# Base.net
KiCad netlist of a schematic drawn in Altium Designer
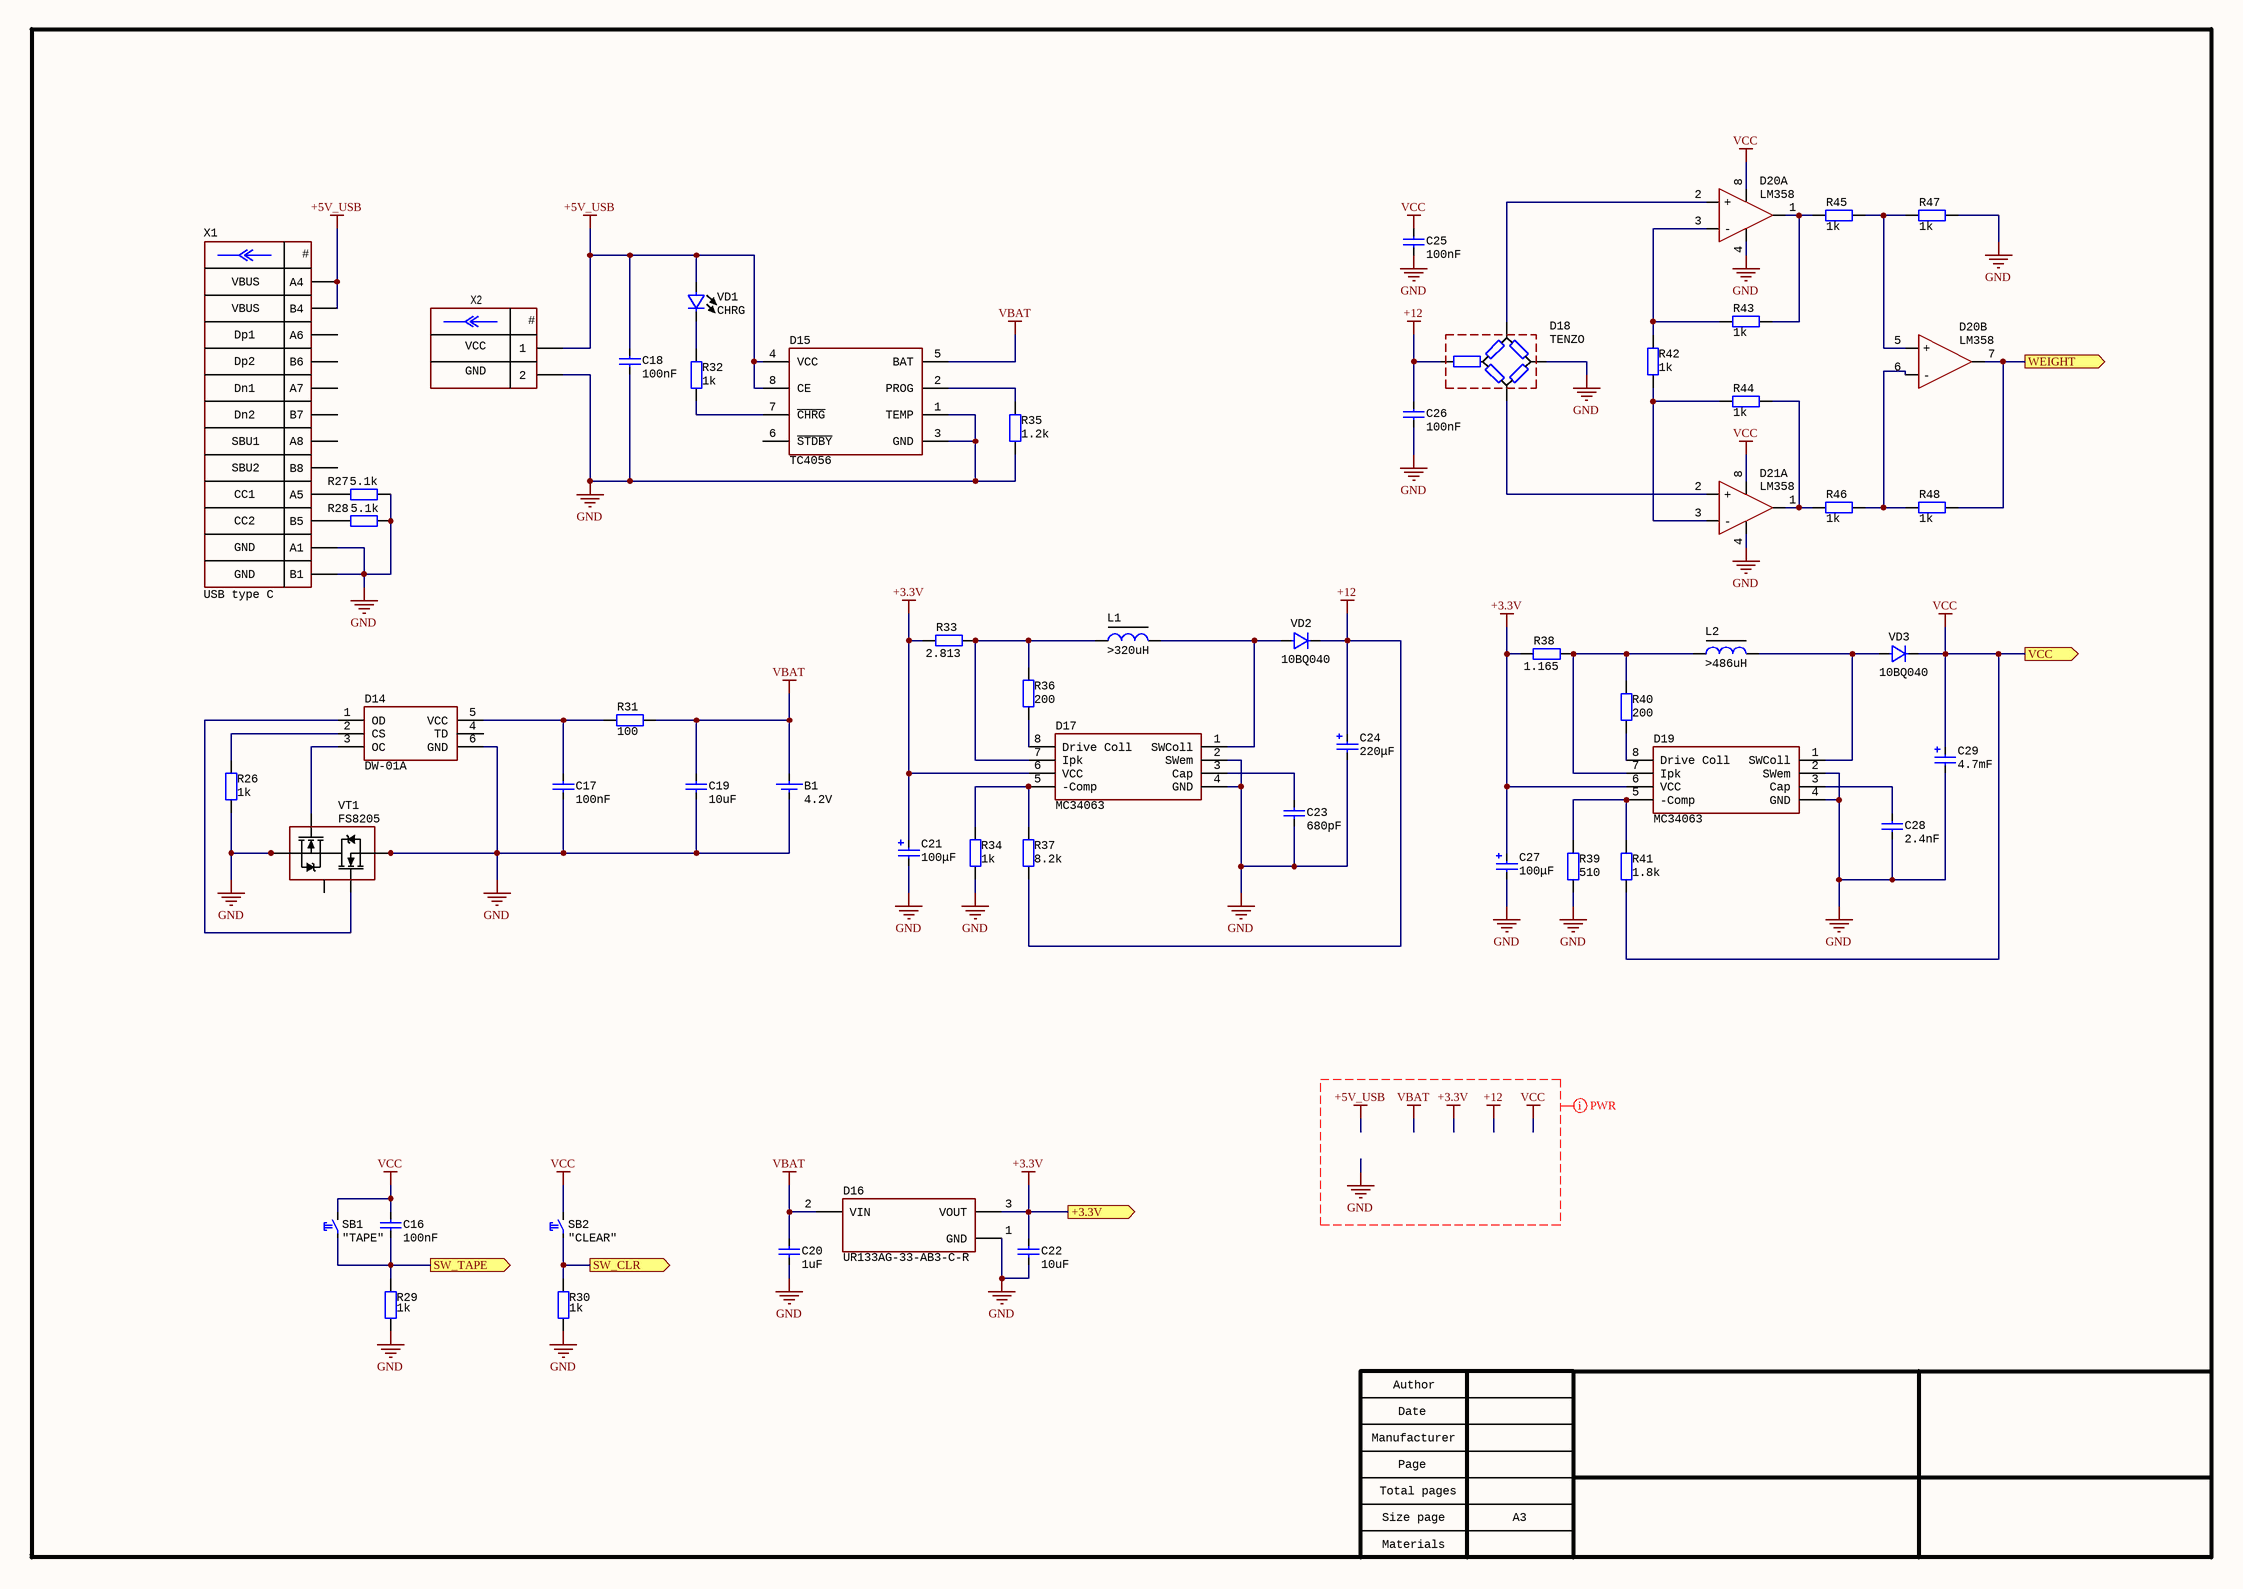
[diagram p0: Base.SchDoc]

(export (version "E")
  (design (tool "Eeschema 10.0.6"))
  (components
    (comp (ref "B1")
      (value "~")
      (footprint "CON: PLS-2")
      (fields
        (field (name "MANUFACTURER") "ALLOYSEED")
        (field (name "VALUEMANUFACTURERPARTNUMBER") "Single holder 18650, 4.2V")
        (field (name "PARTNUMBER") "Holder 18650")
        (field (name "VOLTAGEMAX") "4.2V")
      )
      (libsource (lib "connector") (part "Battery PLS-2"))
    )
    (comp (ref "C16")
      (value "100nF")
      (footprint "CAP: ECHU(X) K (0603)")
      (fields
        (field (name "MANUFACTURER") "Epcos")
        (field (name "PARTNUMBER") "B32774D4106K000")
        (field (name "VALUEMANUFACTURERPARTNUMBER") "Film capacitor, 100nF, 15VDC, ±10%, 10.9mOhm, 31.5x15 mm, -40...+105°C")
      )
      (libsource (lib "capacitor") (part "Film"))
    )
    (comp (ref "C17")
      (value "100nF")
      (footprint "CAP: ECHU(X) K (0603)")
      (fields
        (field (name "MANUFACTURER") "Epcos")
        (field (name "PARTNUMBER") "B32774D4106K000")
        (field (name "VALUEMANUFACTURERPARTNUMBER") "Film capacitor, 100nF, 15VDC, ±10%, 10.9mOhm, 31.5x15 mm, -40...+105°C")
      )
      (libsource (lib "capacitor") (part "Film"))
    )
    (comp (ref "C18")
      (value "100nF")
      (footprint "CAP: ECHU(X) K (0603)")
      (fields
        (field (name "MANUFACTURER") "Epcos")
        (field (name "PARTNUMBER") "B32774D4106K000")
        (field (name "VALUEMANUFACTURERPARTNUMBER") "Film capacitor, 100nF, 15VDC, ±10%, 10.9mOhm, 31.5x15 mm, -40...+105°C")
      )
      (libsource (lib "capacitor") (part "Film"))
    )
    (comp (ref "C19")
      (value "10uF")
      (footprint "CAP: ECHU(X) K (0603)")
      (fields
        (field (name "MANUFACTURER") "Epcos")
        (field (name "PARTNUMBER") "B32774D4106K000")
        (field (name "VALUEMANUFACTURERPARTNUMBER") "Film capacitor, 10uF, 15VDC, ±10%, 10.9mOhm, 31.5x15 mm, -40...+105°C")
      )
      (libsource (lib "capacitor") (part "Film"))
    )
    (comp (ref "C20")
      (value "1uF")
      (footprint "CAP: ECHU(X) K (0603)")
      (fields
        (field (name "MANUFACTURER") "Epcos")
        (field (name "PARTNUMBER") "B32774D4106K000")
        (field (name "VALUEMANUFACTURERPARTNUMBER") "Film capacitor, 1uF, 15VDC, ±10%, 10.9mOhm, 31.5x15 mm, -40...+105°C")
      )
      (libsource (lib "capacitor") (part "Film"))
    )
    (comp (ref "C21")
      (value "100μF")
      (footprint "CAP: TANTAL-E")
      (fields
        (field (name "MANUFACTURER") "AVX")
        (field (name "PARTNUMBER") "F930J107KAAAJ6")
        (field (name "VALUEMANUFACTURERPARTNUMBER") "Tantalum capacitor, 100μF, 6.3V, ±10%, 2Ohm, case A (3216), -55...+125°C")
      )
      (libsource (lib "capacitor") (part "Tantal"))
    )
    (comp (ref "C22")
      (value "10uF")
      (footprint "CAP: ECHU(X) K (0603)")
      (fields
        (field (name "MANUFACTURER") "Epcos")
        (field (name "PARTNUMBER") "B32774D4106K000")
        (field (name "VALUEMANUFACTURERPARTNUMBER") "Film capacitor, 10uF, 15VDC, ±10%, 10.9mOhm, 31.5x15 mm, -40...+105°C")
      )
      (libsource (lib "capacitor") (part "Film"))
    )
    (comp (ref "C23")
      (value "680pF")
      (footprint "CAP: ECHU(X) J (0805)")
      (fields
        (field (name "MANUFACTURER") "Epcos")
        (field (name "PARTNUMBER") "B32774D4106K000")
        (field (name "VALUEMANUFACTURERPARTNUMBER") "Film capacitor, 680pF, 15VDC, ±10%, 10.9mOhm, 31.5x15 mm, -40...+105°C")
      )
      (libsource (lib "capacitor") (part "Film"))
    )
    (comp (ref "C24")
      (value "220μF")
      (footprint "CAP: TANTAL-E")
      (fields
        (field (name "MANUFACTURER") "AVX")
        (field (name "PARTNUMBER") "F930J107KAAAJ6")
        (field (name "VALUEMANUFACTURERPARTNUMBER") "Tantalum capacitor, 220μF, 6.3V, ±10%, 2Ohm, case A (3216), -55...+125°C")
      )
      (libsource (lib "capacitor") (part "Tantal"))
    )
    (comp (ref "C25")
      (value "100nF")
      (footprint "CAP: ECHU(X) K (0603)")
      (fields
        (field (name "MANUFACTURER") "Epcos")
        (field (name "PARTNUMBER") "B32774D4106K000")
        (field (name "VALUEMANUFACTURERPARTNUMBER") "Film capacitor, 100nF, 15VDC, ±10%, 10.9mOhm, 31.5x15 mm, -40...+105°C")
      )
      (libsource (lib "capacitor") (part "Film"))
    )
    (comp (ref "C26")
      (value "100nF")
      (footprint "CAP: ECHU(X) K (0603)")
      (fields
        (field (name "MANUFACTURER") "Epcos")
        (field (name "PARTNUMBER") "B32774D4106K000")
        (field (name "VALUEMANUFACTURERPARTNUMBER") "Film capacitor, 100nF, 15VDC, ±10%, 10.9mOhm, 31.5x15 mm, -40...+105°C")
      )
      (libsource (lib "capacitor") (part "Film"))
    )
    (comp (ref "C27")
      (value "100μF")
      (footprint "CAP: TANTAL-E")
      (fields
        (field (name "MANUFACTURER") "AVX")
        (field (name "PARTNUMBER") "F930J107KAAAJ6")
        (field (name "VALUEMANUFACTURERPARTNUMBER") "Tantalum capacitor, 100μF, 6.3V, ±10%, 2Ohm, case A (3216), -55...+125°C")
      )
      (libsource (lib "capacitor") (part "Tantal"))
    )
    (comp (ref "C28")
      (value "2.4nF")
      (footprint "CAP: ECHU(X) J (0805)")
      (fields
        (field (name "MANUFACTURER") "Epcos")
        (field (name "PARTNUMBER") "B32774D4106K000")
        (field (name "VALUEMANUFACTURERPARTNUMBER") "Film capacitor, 2.4nF, 15VDC, ±10%, 10.9mOhm, 31.5x15 mm, -40...+105°C")
      )
      (libsource (lib "capacitor") (part "Film"))
    )
    (comp (ref "C29")
      (value "4.7mF")
      (footprint "CAP: TANTAL-E")
      (fields
        (field (name "MANUFACTURER") "AVX")
        (field (name "PARTNUMBER") "F930J107KAAAJ6")
        (field (name "VALUEMANUFACTURERPARTNUMBER") "Tantalum capacitor, 4.7mF, 6.3V, ±10%, 2Ohm, case A (3216), -55...+125°C")
      )
      (libsource (lib "capacitor") (part "Tantal"))
    )
    (comp (ref "D14")
      (value "DW-01A")
      (footprint "SOT23-6")
      (fields
        (field (name "PARTNUMBER") "LTC4056ETS8-4.2#TRMPBF")
        (field (name "MANUFACTURER") "Linear Technology")
      )
      (libsource (lib "ic-power-supply") (part "DW-01A"))
    )
    (comp (ref "D15")
      (value "TC4056")
      (footprint "8-SOIC")
      (fields
        (field (name "PARTNUMBER") "LTC4056ETS8-4.2#TRMPBF")
        (field (name "MANUFACTURER") "Linear Technology")
      )
      (libsource (lib "ic-power-supply") (part "TC4056"))
    )
    (comp (ref "D16")
      (value "~")
      (footprint "SOT-89")
      (description "Linear voltage regulator")
      (fields
        (field (name "MANUFACTURER") "Diodes Incorporated")
        (field (name "VALUEMANUFACTURERPARTNUMBER") "Linear voltage regulator, input 2.5...6V, 0.7V, output 1.8V, 0.3A, -40...+85°C, SOT23-5")
        (field (name "PARTNUMBER") "UR133AG-33-AB3-C-R")
      )
      (libsource (lib "ic-power-supply") (part "UR133AG-33-AB3-C-R"))
    )
    (comp (ref "D17")
      (value "~")
      (footprint "8-SOIC")
      (description "DC/DC")
      (fields
        (field (name "MANUFACTURER") "Diodes Incorporated")
        (field (name "VALUEMANUFACTURERPARTNUMBER") "DC/DC boost converter, input 2.6...16V, 1.5MHz, output 3...29V, 0.5A, -40...+85°C, SOT23-5")
        (field (name "PARTNUMBER") "MC34063")
      )
      (libsource (lib "ic-power-supply") (part "MC34063"))
    )
    (comp (ref "D18") (value "TENZO") (footprint "CON: PLS-4") (libsource (lib "Scales") (part "TENZO")))
    (comp (ref "D19")
      (value "~")
      (footprint "8-SOIC")
      (description "DC/DC")
      (fields
        (field (name "MANUFACTURER") "Diodes Incorporated")
        (field (name "VALUEMANUFACTURERPARTNUMBER") "DC/DC boost converter, input 2.6...16V, 1.5MHz, output 3...29V, 0.5A, -40...+85°C, SOT23-5")
        (field (name "PARTNUMBER") "MC34063")
      )
      (libsource (lib "ic-power-supply") (part "MC34063"))
    )
    (comp (ref "D20")
      (value "LM358")
      (footprint "8-SOIC")
      (description "Comparator")
      (fields
        (field (name "MANUFACTURER") "Microchip Technology")
        (field (name "VALUEMANUFACTURERPARTNUMBER") "IC comparator, Rail-to-Rail, 1.6...5.5V, -40...+85°C, SOT23-5")
      )
      (libsource (lib "ic-op-comp") (part "LM358"))
    )
    (comp (ref "D21")
      (value "LM358")
      (footprint "8-SOIC")
      (description "Comparator")
      (fields
        (field (name "MANUFACTURER") "Microchip Technology")
        (field (name "VALUEMANUFACTURERPARTNUMBER") "IC comparator, Rail-to-Rail, 1.6...5.5V, -40...+85°C, SOT23-5")
      )
      (libsource (lib "ic-op-comp") (part "LM358"))
    )
    (comp (ref "L1")
      (value "~")
      (footprint "LQH55")
      (fields
        (field (name "MANUFACTURER") "Asia")
        (field (name "VALUEMANUFACTURERPARTNUMBER") "Transformer, >320uH, 0...250 Ohm")
        (field (name "PARTNUMBER") "DL-CT1005A")
        (field (name "VOLTAGE") ">320uH")
      )
      (libsource (lib "transformer") (part "Current_CT1005A"))
    )
    (comp (ref "L2")
      (value "~")
      (footprint "LQH55")
      (fields
        (field (name "MANUFACTURER") "Asia")
        (field (name "VALUEMANUFACTURERPARTNUMBER") "Transformer, >486uH, 0...250 Ohm")
        (field (name "PARTNUMBER") "DL-CT1005A")
        (field (name "VOLTAGE") ">486uH")
      )
      (libsource (lib "transformer") (part "Current_CT1005A"))
    )
    (comp (ref "R26")
      (value "1k")
      (footprint "RES: 0402")
      (fields
        (field (name "MANUFACTURER") "Yageo")
        (field (name "PARTNUMBER") "RC0201JR-07100RL")
        (field (name "VALUEMANUFACTURERPARTNUMBER") "Resistor film, 1k, ±5%, 0201, 0.05W, -55...+125°C")
      )
      (libsource (lib "") (part "Resistor_2_2"))
    )
    (comp (ref "R27")
      (value "5.1k")
      (footprint "RES: 0402")
      (fields
        (field (name "MANUFACTURER") "Yageo")
        (field (name "PARTNUMBER") "RC0201JR-07100RL")
        (field (name "VALUEMANUFACTURERPARTNUMBER") "Resistor film, 5.1k, ±5%, 0201, 0.05W, -55...+125°C")
      )
      (libsource (lib "resistor") (part "Resistor_2"))
    )
    (comp (ref "R28")
      (value "5.1k")
      (footprint "RES: 0402")
      (fields
        (field (name "MANUFACTURER") "Yageo")
        (field (name "PARTNUMBER") "RC0201JR-07100RL")
        (field (name "VALUEMANUFACTURERPARTNUMBER") "Resistor film, 5.1k, ±5%, 0201, 0.05W, -55...+125°C")
      )
      (libsource (lib "resistor") (part "Resistor_2"))
    )
    (comp (ref "R29")
      (value "1k")
      (footprint "RES: 0402")
      (fields
        (field (name "MANUFACTURER") "Yageo")
        (field (name "PARTNUMBER") "RC0201JR-07100RL")
        (field (name "VALUEMANUFACTURERPARTNUMBER") "Resistor film, 1k, ±5%, 0201, 0.05W, -55...+125°C")
      )
      (libsource (lib "") (part "Resistor_2_1"))
    )
    (comp (ref "R30")
      (value "1k")
      (footprint "RES: 0402")
      (fields
        (field (name "MANUFACTURER") "Yageo")
        (field (name "PARTNUMBER") "RC0201JR-07100RL")
        (field (name "VALUEMANUFACTURERPARTNUMBER") "Resistor film, 1k, ±5%, 0201, 0.05W, -55...+125°C")
      )
      (libsource (lib "") (part "Resistor_2_1"))
    )
    (comp (ref "R31")
      (value "100")
      (footprint "RES: 0402")
      (fields
        (field (name "MANUFACTURER") "Yageo")
        (field (name "PARTNUMBER") "RC0201JR-07100RL")
        (field (name "VALUEMANUFACTURERPARTNUMBER") "Resistor film, 100, ±5%, 0201, 0.05W, -55...+125°C")
      )
      (libsource (lib "resistor") (part "Resistor_2"))
    )
    (comp (ref "R32")
      (value "1k")
      (footprint "RES: 0402")
      (fields
        (field (name "MANUFACTURER") "Yageo")
        (field (name "PARTNUMBER") "RC0201JR-07100RL")
        (field (name "VALUEMANUFACTURERPARTNUMBER") "Resistor film, 1k, ±5%, 0201, 0.05W, -55...+125°C")
      )
      (libsource (lib "") (part "Resistor_2_2"))
    )
    (comp (ref "R33")
      (value "2.813")
      (footprint "RES: 0402")
      (fields
        (field (name "MANUFACTURER") "Yageo")
        (field (name "PARTNUMBER") "RC0201JR-07100RL")
        (field (name "VALUEMANUFACTURERPARTNUMBER") "Resistor film, 2.813, ±5%, 0201, 0.05W, -55...+125°C")
      )
      (libsource (lib "") (part "Resistor_2_1"))
    )
    (comp (ref "R34")
      (value "1k")
      (footprint "RES: 0402")
      (fields
        (field (name "MANUFACTURER") "Yageo")
        (field (name "PARTNUMBER") "RC0201JR-07100RL")
        (field (name "VALUEMANUFACTURERPARTNUMBER") "Resistor film, 1k, ±5%, 0201, 0.05W, -55...+125°C")
      )
      (libsource (lib "") (part "Resistor_2_3"))
    )
    (comp (ref "R35")
      (value "1.2k")
      (footprint "RES: 0402")
      (fields
        (field (name "MANUFACTURER") "Yageo")
        (field (name "PARTNUMBER") "RC0201JR-07100RL")
        (field (name "VALUEMANUFACTURERPARTNUMBER") "Resistor film, 1.2k, ±5%, 0201, 0.05W, -55...+125°C")
      )
      (libsource (lib "") (part "Resistor_2_2"))
    )
    (comp (ref "R36")
      (value "200")
      (footprint "RES: 0402")
      (fields
        (field (name "MANUFACTURER") "Yageo")
        (field (name "PARTNUMBER") "RC0201JR-07100RL")
        (field (name "VALUEMANUFACTURERPARTNUMBER") "Resistor film, 200, ±5%, 0201, 0.05W, -55...+125°C")
      )
      (libsource (lib "") (part "Resistor_2_3"))
    )
    (comp (ref "R37")
      (value "8.2k")
      (footprint "RES: 0402")
      (fields
        (field (name "MANUFACTURER") "Yageo")
        (field (name "PARTNUMBER") "RC0201JR-07100RL")
        (field (name "VALUEMANUFACTURERPARTNUMBER") "Resistor film, 8.2k, ±5%, 0201, 0.05W, -55...+125°C")
      )
      (libsource (lib "") (part "Resistor_2_3"))
    )
    (comp (ref "R38")
      (value "1.165")
      (footprint "RES: 0402")
      (fields
        (field (name "MANUFACTURER") "Yageo")
        (field (name "PARTNUMBER") "RC0201JR-07100RL")
        (field (name "VALUEMANUFACTURERPARTNUMBER") "Resistor film, 1.165, ±5%, 0201, 0.05W, -55...+125°C")
      )
      (libsource (lib "") (part "Resistor_2_1"))
    )
    (comp (ref "R39")
      (value "510")
      (footprint "RES: 0402")
      (fields
        (field (name "MANUFACTURER") "Yageo")
        (field (name "PARTNUMBER") "RC0201JR-07100RL")
        (field (name "VALUEMANUFACTURERPARTNUMBER") "Resistor film, 510, ±5%, 0201, 0.05W, -55...+125°C")
      )
      (libsource (lib "") (part "Resistor_2_3"))
    )
    (comp (ref "R40")
      (value "200")
      (footprint "RES: 0402")
      (fields
        (field (name "MANUFACTURER") "Yageo")
        (field (name "PARTNUMBER") "RC0201JR-07100RL")
        (field (name "VALUEMANUFACTURERPARTNUMBER") "Resistor film, 200, ±5%, 0201, 0.05W, -55...+125°C")
      )
      (libsource (lib "") (part "Resistor_2_3"))
    )
    (comp (ref "R41")
      (value "1.8k")
      (footprint "RES: 0402")
      (fields
        (field (name "MANUFACTURER") "Yageo")
        (field (name "PARTNUMBER") "RC0201JR-07100RL")
        (field (name "VALUEMANUFACTURERPARTNUMBER") "Resistor film, 1.8k, ±5%, 0201, 0.05W, -55...+125°C")
      )
      (libsource (lib "") (part "Resistor_2_3"))
    )
    (comp (ref "R42")
      (value "1k")
      (footprint "RES: 0402")
      (fields
        (field (name "MANUFACTURER") "Yageo")
        (field (name "PARTNUMBER") "RC0201JR-07100RL")
        (field (name "VALUEMANUFACTURERPARTNUMBER") "Resistor film, 1k, ±5%, 0201, 0.05W, -55...+125°C")
      )
      (libsource (lib "") (part "Resistor_2_2"))
    )
    (comp (ref "R43")
      (value "1k")
      (footprint "RES: 0402")
      (fields
        (field (name "MANUFACTURER") "Yageo")
        (field (name "PARTNUMBER") "RC0201JR-07100RL")
        (field (name "VALUEMANUFACTURERPARTNUMBER") "Resistor film, 1k, ±5%, 0201, 0.05W, -55...+125°C")
      )
      (libsource (lib "resistor") (part "Resistor_2"))
    )
    (comp (ref "R44")
      (value "1k")
      (footprint "RES: 0402")
      (fields
        (field (name "MANUFACTURER") "Yageo")
        (field (name "PARTNUMBER") "RC0201JR-07100RL")
        (field (name "VALUEMANUFACTURERPARTNUMBER") "Resistor film, 1k, ±5%, 0201, 0.05W, -55...+125°C")
      )
      (libsource (lib "resistor") (part "Resistor_2"))
    )
    (comp (ref "R45")
      (value "1k")
      (footprint "RES: 0402")
      (fields
        (field (name "MANUFACTURER") "Yageo")
        (field (name "PARTNUMBER") "RC0201JR-07100RL")
        (field (name "VALUEMANUFACTURERPARTNUMBER") "Resistor film, 1k, ±5%, 0201, 0.05W, -55...+125°C")
      )
      (libsource (lib "") (part "Resistor_2_3"))
    )
    (comp (ref "R46")
      (value "1k")
      (footprint "RES: 0402")
      (fields
        (field (name "MANUFACTURER") "Yageo")
        (field (name "PARTNUMBER") "RC0201JR-07100RL")
        (field (name "VALUEMANUFACTURERPARTNUMBER") "Resistor film, 1k, ±5%, 0201, 0.05W, -55...+125°C")
      )
      (libsource (lib "") (part "Resistor_2_3"))
    )
    (comp (ref "R47")
      (value "1k")
      (footprint "RES: 0402")
      (fields
        (field (name "MANUFACTURER") "Yageo")
        (field (name "PARTNUMBER") "RC0201JR-07100RL")
        (field (name "VALUEMANUFACTURERPARTNUMBER") "Resistor film, 1k, ±5%, 0201, 0.05W, -55...+125°C")
      )
      (libsource (lib "") (part "Resistor_2_3"))
    )
    (comp (ref "R48")
      (value "1k")
      (footprint "RES: 0402")
      (fields
        (field (name "MANUFACTURER") "Yageo")
        (field (name "PARTNUMBER") "RC0201JR-07100RL")
        (field (name "VALUEMANUFACTURERPARTNUMBER") "Resistor film, 1k, ±5%, 0201, 0.05W, -55...+125°C")
      )
      (libsource (lib "") (part "Resistor_2_3"))
    )
    (comp (ref "SB1")
      (value "~")
      (footprint "BUT: 6x3.5 SMD")
      (fields
        (field (name "MANUFACTURER") "TE Connectivity")
        (field (name "VALUEMANUFACTURERPARTNUMBER") "Tactile button, 6x6mm")
        (field (name "PARTNUMBER") "FSM2JSMAATR")
        (field (name "COMMENTTEXT") "\"TAPE\"")
      )
      (libsource (lib "electromechanics") (part "Button_tactile"))
    )
    (comp (ref "SB2")
      (value "~")
      (footprint "BUT: 6x3.5 SMD")
      (fields
        (field (name "MANUFACTURER") "TE Connectivity")
        (field (name "VALUEMANUFACTURERPARTNUMBER") "Tactile button, 6x6mm")
        (field (name "PARTNUMBER") "FSM2JSMAATR")
        (field (name "COMMENTTEXT") "\"CLEAR\"")
      )
      (libsource (lib "electromechanics") (part "Button_tactile"))
    )
    (comp (ref "VD1")
      (value "~")
      (footprint "LED: 0402B")
      (fields
        (field (name "VALUEMANUFACTURERPARTNUMBER") "LED, Green, *, *, *, -55...+150°C")
        (field (name "COLOR") "CHRG")
      )
      (libsource (lib "diode") (part "LED_single"))
    )
    (comp (ref "VD2")
      (value "~")
      (footprint "DIODE: SMB")
      (fields
        (field (name "MANUFACTURER") "Micro Commercial")
        (field (name "VALUEMANUFACTURERPARTNUMBER") "Single diode, 75V, 150mA, 1V, 4ns, SOD-323, -55...+150°C")
        (field (name "VOLTAGE") "75V")
        (field (name "PARTNUMBER") "10BQ040")
      )
      (libsource (lib "diode") (part "Diode_single"))
    )
    (comp (ref "VD3")
      (value "~")
      (footprint "DIODE: SMB")
      (fields
        (field (name "MANUFACTURER") "Micro Commercial")
        (field (name "VALUEMANUFACTURERPARTNUMBER") "Single diode, 75V, 150mA, 1V, 4ns, SOD-323, -55...+150°C")
        (field (name "VOLTAGE") "75V")
        (field (name "PARTNUMBER") "10BQ040")
      )
      (libsource (lib "diode") (part "Diode_single"))
    )
    (comp (ref "VT1")
      (value "~")
      (footprint "8-TSOP")
      (fields
        (field (name "MANUFACTURER") "Infineon Technologies")
        (field (name "VALUEMANUFACTURERPARTNUMBER") "MOSFET N-channel transistor, 80V, 7A, 9.1nC, 2.5W, 34mOhm, 756pF, 8-TDSON, -55...+150°C")
        (field (name "PARTNUMBER") "FS8205")
      )
      (libsource (lib "transistor") (part "FS8205"))
    )
    (comp (ref "X1")
      (value "~")
      (footprint "CON: TYPE-C-31-M-12")
      (fields
        (field (name "MANUFACTURER") "Korean Hroparts")
        (field (name "VALUEMANUFACTURERPARTNUMBER") "USB Type C, 3A")
        (field (name "PARTNUMBER") "TYPE-C-31-M-12")
        (field (name "COMMENTTEXT") "USB type C")
      )
      (libsource (lib "connector") (part "Connector_USB_Type_C"))
    )
    (comp (ref "X2")
      (value "~")
      (footprint "CON: PLS-2")
      (fields
        (field (name "MANUFACTURER") "Connfly")
        (field (name "VALUEMANUFACTURERPARTNUMBER") "Connector, 2pin, 2.54mm, 500VAC, 3A")
        (field (name "PARTNUMBER") "PLS-2")
      )
      (libsource (lib "connector") (part "PLS-2"))
    )
  )
  (nets
    (net (code "1") (name "+3.3V") (class "Default")
      (node (ref "C21") (pin "1") (pinfunction "1_1") (pintype "passive"))
      (node (ref "C22") (pin "2") (pinfunction "2_2") (pintype "passive"))
      (node (ref "C27") (pin "1") (pinfunction "1_1") (pintype "passive"))
      (node (ref "D16") (pin "3") (pinfunction "VOUT_3") (pintype "passive"))
      (node (ref "D17") (pin "6") (pinfunction "VCC_6") (pintype "power_in"))
      (node (ref "D19") (pin "6") (pinfunction "VCC_6") (pintype "power_in"))
      (node (ref "R33") (pin "1") (pinfunction "1_1") (pintype "passive"))
      (node (ref "R38") (pin "1") (pinfunction "1_1") (pintype "passive"))
    )
    (net (code "2") (name "+5V_USB") (class "Default")
      (node (ref "C18") (pin "2") (pinfunction "2_2") (pintype "passive"))
      (node (ref "D15") (pin "4") (pinfunction "VCC_4") (pintype "passive"))
      (node (ref "D15") (pin "8") (pinfunction "CE_8") (pintype "passive"))
      (node (ref "VD1") (pin "1") (pinfunction "1_1") (pintype "passive"))
      (node (ref "X1") (pin "A4") (pinfunction "A4_A4") (pintype "passive"))
      (node (ref "X1") (pin "B4") (pinfunction "B4_B4") (pintype "passive"))
      (node (ref "X2") (pin "1") (pinfunction "1_1") (pintype "passive"))
    )
    (net (code "3") (name "+12") (class "Default")
      (node (ref "C24") (pin "1") (pinfunction "1_1") (pintype "passive"))
      (node (ref "C26") (pin "2") (pinfunction "2_2") (pintype "passive"))
      (node (ref "D18") (pin "1") (pinfunction "1_1") (pintype "passive"))
      (node (ref "R37") (pin "2") (pinfunction "2_2") (pintype "passive"))
      (node (ref "VD2") (pin "2") (pinfunction "2_2") (pintype "passive"))
    )
    (net (code "4") (name "/SW_CLR") (class "Default")
      (node (ref "R30") (pin "2") (pinfunction "2_2") (pintype "passive"))
      (node (ref "SB2") (pin "1") (pinfunction "1_1") (pintype "passive"))
    )
    (net (code "5") (name "/SW_TAPE") (class "Default")
      (node (ref "C16") (pin "2") (pinfunction "2_2") (pintype "passive"))
      (node (ref "R29") (pin "2") (pinfunction "2_2") (pintype "passive"))
      (node (ref "SB1") (pin "1") (pinfunction "1_1") (pintype "passive"))
    )
    (net (code "6") (name "/WEIGHT") (class "Default")
      (node (ref "D20") (pin "7") (pintype "power_in"))
      (node (ref "R48") (pin "1") (pinfunction "1_1") (pintype "passive"))
    )
    (net (code "7") (name "GND") (class "Default")
      (node (ref "B1") (pin "2") (pinfunction "-_2") (pintype "power_in"))
      (node (ref "C17") (pin "1") (pinfunction "1_1") (pintype "passive"))
      (node (ref "C18") (pin "1") (pinfunction "1_1") (pintype "passive"))
      (node (ref "C19") (pin "2") (pinfunction "2_2") (pintype "passive"))
      (node (ref "C20") (pin "1") (pinfunction "1_1") (pintype "passive"))
      (node (ref "C21") (pin "2") (pinfunction "2_2") (pintype "passive"))
      (node (ref "C22") (pin "1") (pinfunction "1_1") (pintype "passive"))
      (node (ref "C23") (pin "1") (pinfunction "1_1") (pintype "passive"))
      (node (ref "C24") (pin "2") (pinfunction "2_2") (pintype "passive"))
      (node (ref "C25") (pin "1") (pinfunction "1_1") (pintype "passive"))
      (node (ref "C26") (pin "1") (pinfunction "1_1") (pintype "passive"))
      (node (ref "C27") (pin "2") (pinfunction "2_2") (pintype "passive"))
      (node (ref "C28") (pin "1") (pinfunction "1_1") (pintype "passive"))
      (node (ref "C29") (pin "2") (pinfunction "2_2") (pintype "passive"))
      (node (ref "D14") (pin "6") (pinfunction "GND_6") (pintype "passive"))
      (node (ref "D15") (pin "1") (pinfunction "TEMP_1") (pintype "passive"))
      (node (ref "D15") (pin "3") (pinfunction "GND_3") (pintype "passive"))
      (node (ref "D16") (pin "1") (pinfunction "GND_1") (pintype "passive"))
      (node (ref "D17") (pin "2") (pinfunction "SWem_2") (pintype "passive"))
      (node (ref "D17") (pin "4") (pinfunction "GND_4") (pintype "power_in"))
      (node (ref "D18") (pin "4") (pinfunction "4_4") (pintype "passive"))
      (node (ref "D19") (pin "2") (pinfunction "SWem_2") (pintype "passive"))
      (node (ref "D19") (pin "4") (pinfunction "GND_4") (pintype "power_in"))
      (node (ref "D20") (pin "4") (pintype "power_in"))
      (node (ref "D21") (pin "4") (pintype "power_in"))
      (node (ref "R26") (pin "2") (pinfunction "2_2") (pintype "passive"))
      (node (ref "R27") (pin "2") (pinfunction "2_2") (pintype "passive"))
      (node (ref "R28") (pin "2") (pinfunction "2_2") (pintype "passive"))
      (node (ref "R29") (pin "1") (pinfunction "1_1") (pintype "passive"))
      (node (ref "R30") (pin "1") (pinfunction "1_1") (pintype "passive"))
      (node (ref "R34") (pin "2") (pinfunction "2_2") (pintype "passive"))
      (node (ref "R35") (pin "2") (pinfunction "2_2") (pintype "passive"))
      (node (ref "R39") (pin "2") (pinfunction "2_2") (pintype "passive"))
      (node (ref "R47") (pin "1") (pinfunction "1_1") (pintype "passive"))
      (node (ref "VT1") (pin "2") (pinfunction "S1_2") (pintype "passive"))
      (node (ref "VT1") (pin "3") (pinfunction "S1_3") (pintype "passive"))
      (node (ref "VT1") (pin "6") (pinfunction "S2_6") (pintype "passive"))
      (node (ref "VT1") (pin "7") (pinfunction "S2_7") (pintype "passive"))
      (node (ref "X1") (pin "A1") (pinfunction "A1_A1") (pintype "passive"))
      (node (ref "X1") (pin "B1") (pinfunction "B1_B1") (pintype "passive"))
      (node (ref "X2") (pin "2") (pinfunction "2_2") (pintype "passive"))
    )
    (net (code "8") (name "Net-(D14-CS)") (class "Default")
      (node (ref "D14") (pin "2") (pinfunction "CS_2") (pintype "passive"))
      (node (ref "R26") (pin "1") (pinfunction "1_1") (pintype "passive"))
    )
    (net (code "9") (name "Net-(D14-OC)") (class "Default")
      (node (ref "D14") (pin "3") (pinfunction "OC_3") (pintype "passive"))
      (node (ref "VT1") (pin "4") (pinfunction "G1_4") (pintype "passive"))
    )
    (net (code "10") (name "Net-(D14-OD)") (class "Default")
      (node (ref "D14") (pin "1") (pinfunction "OD_1") (pintype "passive"))
      (node (ref "VT1") (pin "5") (pinfunction "G2_5") (pintype "passive"))
    )
    (net (code "11") (name "Net-(D14-VCC)") (class "Default")
      (node (ref "C17") (pin "2") (pinfunction "2_2") (pintype "passive"))
      (node (ref "D14") (pin "5") (pinfunction "VCC_5") (pintype "passive"))
      (node (ref "R31") (pin "1") (pinfunction "1_1") (pintype "passive"))
    )
    (net (code "12") (name "Net-(D15-PROG)") (class "Default")
      (node (ref "D15") (pin "2") (pinfunction "PROG_2") (pintype "passive"))
      (node (ref "R35") (pin "1") (pinfunction "1_1") (pintype "passive"))
    )
    (net (code "13") (name "Net-(D15-~{CHRG})") (class "Default")
      (node (ref "D15") (pin "7") (pinfunction "~{CHRG}_7") (pintype "passive"))
      (node (ref "R32") (pin "2") (pinfunction "2_2") (pintype "passive"))
    )
    (net (code "14") (name "Net-(D17--Comp)") (class "Default")
      (node (ref "D17") (pin "5") (pinfunction "-Comp_5") (pintype "passive"))
      (node (ref "R34") (pin "1") (pinfunction "1_1") (pintype "passive"))
      (node (ref "R37") (pin "1") (pinfunction "1_1") (pintype "passive"))
    )
    (net (code "15") (name "Net-(D17-Cap)") (class "Default")
      (node (ref "C23") (pin "2") (pinfunction "2_2") (pintype "passive"))
      (node (ref "D17") (pin "3") (pinfunction "Cap_3") (pintype "passive"))
    )
    (net (code "16") (name "Net-(D17-Drive_Coll)") (class "Default")
      (node (ref "D17") (pin "8") (pinfunction "Drive_Coll_8") (pintype "passive"))
      (node (ref "R36") (pin "2") (pinfunction "2_2") (pintype "passive"))
    )
    (net (code "17") (name "Net-(D17-Ipk)") (class "Default")
      (node (ref "D17") (pin "7") (pinfunction "Ipk_7") (pintype "passive"))
      (node (ref "L1") (pin "2") (pinfunction "2_2") (pintype "power_in"))
      (node (ref "R33") (pin "2") (pinfunction "2_2") (pintype "passive"))
      (node (ref "R36") (pin "1") (pinfunction "1_1") (pintype "passive"))
    )
    (net (code "18") (name "Net-(D17-SWColl)") (class "Default")
      (node (ref "D17") (pin "1") (pinfunction "SWColl_1") (pintype "passive"))
      (node (ref "L1") (pin "1") (pinfunction "1_1") (pintype "power_in"))
      (node (ref "VD2") (pin "1") (pinfunction "1_1") (pintype "passive"))
    )
    (net (code "19") (name "Net-(D19--Comp)") (class "Default")
      (node (ref "D19") (pin "5") (pinfunction "-Comp_5") (pintype "passive"))
      (node (ref "R39") (pin "1") (pinfunction "1_1") (pintype "passive"))
      (node (ref "R41") (pin "1") (pinfunction "1_1") (pintype "passive"))
    )
    (net (code "20") (name "Net-(D19-Cap)") (class "Default")
      (node (ref "C28") (pin "2") (pinfunction "2_2") (pintype "passive"))
      (node (ref "D19") (pin "3") (pinfunction "Cap_3") (pintype "passive"))
    )
    (net (code "21") (name "Net-(D19-Drive_Coll)") (class "Default")
      (node (ref "D19") (pin "8") (pinfunction "Drive_Coll_8") (pintype "passive"))
      (node (ref "R40") (pin "2") (pinfunction "2_2") (pintype "passive"))
    )
    (net (code "22") (name "Net-(D19-Ipk)") (class "Default")
      (node (ref "D19") (pin "7") (pinfunction "Ipk_7") (pintype "passive"))
      (node (ref "L2") (pin "2") (pinfunction "2_2") (pintype "power_in"))
      (node (ref "R38") (pin "2") (pinfunction "2_2") (pintype "passive"))
      (node (ref "R40") (pin "1") (pinfunction "1_1") (pintype "passive"))
    )
    (net (code "23") (name "Net-(D19-SWColl)") (class "Default")
      (node (ref "D19") (pin "1") (pinfunction "SWColl_1") (pintype "passive"))
      (node (ref "L2") (pin "1") (pinfunction "1_1") (pintype "power_in"))
      (node (ref "VD3") (pin "1") (pinfunction "1_1") (pintype "passive"))
    )
    (net (code "24") (name "Net-(D20-Pad1)") (class "Default")
      (node (ref "D20") (pin "1") (pintype "power_in"))
      (node (ref "R43") (pin "2") (pinfunction "2_2") (pintype "passive"))
      (node (ref "R45") (pin "2") (pinfunction "2_2") (pintype "passive"))
    )
    (net (code "25") (name "Net-(D20A-+)") (class "Default")
      (node (ref "D18") (pin "2") (pinfunction "2_2") (pintype "passive"))
      (node (ref "D20") (pin "2") (pinfunction "+_2") (pintype "passive"))
    )
    (net (code "26") (name "Net-(D20A--)") (class "Default")
      (node (ref "D20") (pin "3") (pinfunction "-_3") (pintype "passive"))
      (node (ref "R42") (pin "1") (pinfunction "1_1") (pintype "passive"))
      (node (ref "R43") (pin "1") (pinfunction "1_1") (pintype "passive"))
    )
    (net (code "27") (name "Net-(D20B-+)") (class "Default")
      (node (ref "D20") (pin "5") (pinfunction "+_5") (pintype "passive"))
      (node (ref "R45") (pin "1") (pinfunction "1_1") (pintype "passive"))
      (node (ref "R47") (pin "2") (pinfunction "2_2") (pintype "passive"))
    )
    (net (code "28") (name "Net-(D20B--)") (class "Default")
      (node (ref "D20") (pin "6") (pinfunction "-_6") (pintype "passive"))
      (node (ref "R46") (pin "1") (pinfunction "1_1") (pintype "passive"))
      (node (ref "R48") (pin "2") (pinfunction "2_2") (pintype "passive"))
    )
    (net (code "29") (name "Net-(D21-Pad1)") (class "Default")
      (node (ref "D21") (pin "1") (pintype "power_in"))
      (node (ref "R44") (pin "2") (pinfunction "2_2") (pintype "passive"))
      (node (ref "R46") (pin "2") (pinfunction "2_2") (pintype "passive"))
    )
    (net (code "30") (name "Net-(D21A-+)") (class "Default")
      (node (ref "D18") (pin "3") (pinfunction "3_3") (pintype "passive"))
      (node (ref "D21") (pin "2") (pinfunction "+_2") (pintype "passive"))
    )
    (net (code "31") (name "Net-(D21A--)") (class "Default")
      (node (ref "D21") (pin "3") (pinfunction "-_3") (pintype "passive"))
      (node (ref "R42") (pin "2") (pinfunction "2_2") (pintype "passive"))
      (node (ref "R44") (pin "1") (pinfunction "1_1") (pintype "passive"))
    )
    (net (code "32") (name "Net-(R27-Pad1)") (class "Default")
      (node (ref "R27") (pin "1") (pinfunction "1_1") (pintype "passive"))
      (node (ref "X1") (pin "A5") (pinfunction "A5_A5") (pintype "passive"))
    )
    (net (code "33") (name "Net-(R28-Pad1)") (class "Default")
      (node (ref "R28") (pin "1") (pinfunction "1_1") (pintype "passive"))
      (node (ref "X1") (pin "B5") (pinfunction "B5_B5") (pintype "passive"))
    )
    (net (code "34") (name "Net-(R32-Pad1)") (class "Default")
      (node (ref "R32") (pin "1") (pinfunction "1_1") (pintype "passive"))
      (node (ref "VD1") (pin "2") (pinfunction "2_2") (pintype "passive"))
    )
    (net (code "35") (name "Net-(VT1-D12-Pad1)") (class "Default")
      (node (ref "VT1") (pin "1") (pinfunction "D12_1") (pintype "passive"))
      (node (ref "VT1") (pin "8") (pinfunction "D12_8") (pintype "passive"))
    )
    (net (code "36") (name "VBAT") (class "Default")
      (node (ref "B1") (pin "1") (pinfunction "+_1") (pintype "power_in"))
      (node (ref "C19") (pin "1") (pinfunction "1_1") (pintype "passive"))
      (node (ref "C20") (pin "2") (pinfunction "2_2") (pintype "passive"))
      (node (ref "D15") (pin "5") (pinfunction "BAT_5") (pintype "passive"))
      (node (ref "D16") (pin "2") (pinfunction "VIN_2") (pintype "passive"))
      (node (ref "R31") (pin "2") (pinfunction "2_2") (pintype "passive"))
    )
    (net (code "37") (name "VCC") (class "Default")
      (node (ref "C16") (pin "1") (pinfunction "1_1") (pintype "passive"))
      (node (ref "C25") (pin "2") (pinfunction "2_2") (pintype "passive"))
      (node (ref "C29") (pin "1") (pinfunction "1_1") (pintype "passive"))
      (node (ref "D20") (pin "8") (pintype "power_in"))
      (node (ref "D21") (pin "8") (pintype "power_in"))
      (node (ref "R41") (pin "2") (pinfunction "2_2") (pintype "passive"))
      (node (ref "SB1") (pin "2") (pinfunction "2_2") (pintype "passive"))
      (node (ref "SB2") (pin "2") (pinfunction "2_2") (pintype "passive"))
      (node (ref "VD3") (pin "2") (pinfunction "2_2") (pintype "passive"))
    )
    (net (code "38") (name "unconnected-(D14-TD-Pad4)") (class "Default")
      (node (ref "D14") (pin "4") (pinfunction "TD_4") (pintype "passive"))
    )
    (net (code "39") (name "unconnected-(D15-~{STDBY}-Pad6)") (class "Default")
      (node (ref "D15") (pin "6") (pinfunction "~{STDBY}_6") (pintype "passive"))
    )
    (net (code "40") (name "unconnected-(X1-PadA6)") (class "Default")
      (node (ref "X1") (pin "A6") (pinfunction "A6_A6") (pintype "passive"))
    )
    (net (code "41") (name "unconnected-(X1-PadA7)") (class "Default")
      (node (ref "X1") (pin "A7") (pinfunction "A7_A7") (pintype "passive"))
    )
    (net (code "42") (name "unconnected-(X1-PadA8)") (class "Default")
      (node (ref "X1") (pin "A8") (pinfunction "A8_A8") (pintype "passive"))
    )
    (net (code "43") (name "unconnected-(X1-PadB6)") (class "Default")
      (node (ref "X1") (pin "B6") (pinfunction "B6_B6") (pintype "passive"))
    )
    (net (code "44") (name "unconnected-(X1-PadB7)") (class "Default")
      (node (ref "X1") (pin "B7") (pinfunction "B7_B7") (pintype "passive"))
    )
    (net (code "45") (name "unconnected-(X1-PadB8)") (class "Default")
      (node (ref "X1") (pin "B8") (pinfunction "B8_B8") (pintype "passive"))
    )
  )
)
